# Asteroid-v4.net
KiCad netlist of a schematic drawn in EAGLE
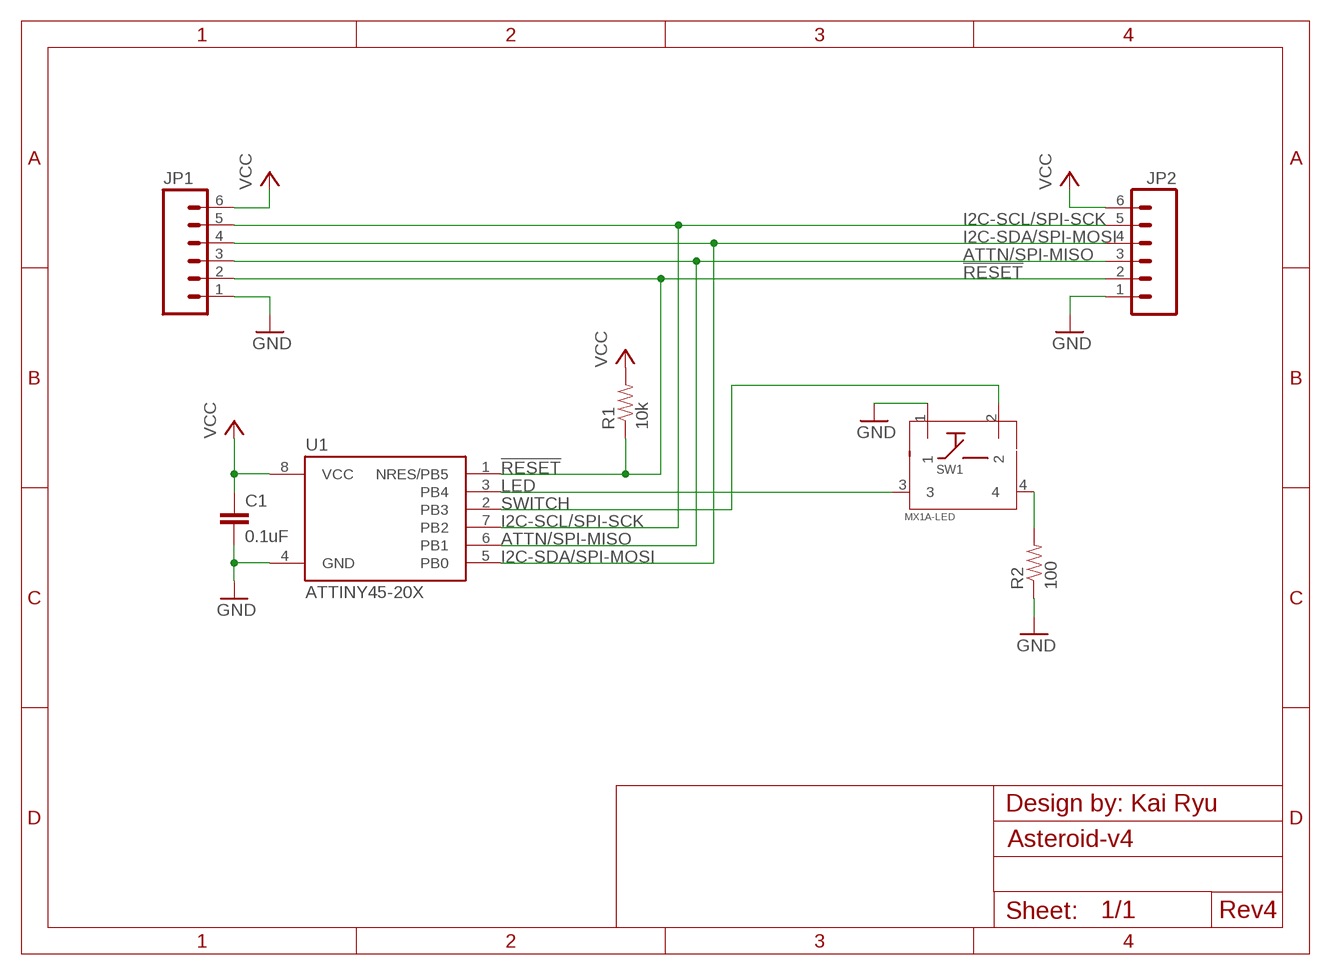
[diagram p0: schematic, sheet 1]

(export (version "E")
  (design (tool "Eeschema 10.0.6"))
  (components
    (comp (ref "C1")
      (value "0.1uF")
      (footprint "eagle-import:0603-CAP")
      (libsource (lib "eagle-import") (part "CAP0603-CAP"))
    )
    (comp (ref "JP1")
      (value "M06SIP")
      (footprint "eagle-import:1X06")
      (libsource (lib "eagle-import") (part "M06SIP"))
    )
    (comp (ref "JP2")
      (value "M06SIP")
      (footprint "eagle-import:1X06")
      (libsource (lib "eagle-import") (part "M06SIP"))
    )
    (comp (ref "R1")
      (value "10k")
      (footprint "eagle-import:0603-RES")
      (libsource (lib "eagle-import") (part "RESISTOR0603-RES"))
    )
    (comp (ref "R2")
      (value "100")
      (footprint "eagle-import:0603-RES")
      (libsource (lib "eagle-import") (part "RESISTOR0603-RES"))
    )
    (comp (ref "SW1")
      (value "MX1A-LED")
      (footprint "eagle-import:MX1A-LED")
      (libsource (lib "eagle-import") (part "MX1A-LED"))
    )
    (comp (ref "U1")
      (value "ATTINY45-20X")
      (footprint "eagle-import:TSSOP8_4MM4")
      (libsource (lib "eagle-import") (part "ATTINY45X-20"))
    )
  )
  (nets
    (net (code "1") (name "/ATTN{slash}SPI-MISO") (class "Default")
      (node (ref "JP1") (pin "3") (pinfunction "3_3") (pintype "passive"))
      (node (ref "JP2") (pin "3") (pinfunction "3_3") (pintype "passive"))
      (node (ref "U1") (pin "6") (pinfunction "PB1_6") (pintype "bidirectional"))
    )
    (net (code "2") (name "/I2C-SCL{slash}SPI-SCK") (class "Default")
      (node (ref "JP1") (pin "5") (pinfunction "5_5") (pintype "passive"))
      (node (ref "JP2") (pin "5") (pinfunction "5_5") (pintype "passive"))
      (node (ref "U1") (pin "7") (pinfunction "PB2_7") (pintype "bidirectional"))
    )
    (net (code "3") (name "/I2C-SDA{slash}SPI-MOSI") (class "Default")
      (node (ref "JP1") (pin "4") (pinfunction "4_4") (pintype "passive"))
      (node (ref "JP2") (pin "4") (pinfunction "4_4") (pintype "passive"))
      (node (ref "U1") (pin "5") (pinfunction "PB0_5") (pintype "bidirectional"))
    )
    (net (code "4") (name "/LED") (class "Default")
      (node (ref "SW1") (pin "3") (pinfunction "3_3") (pintype "passive"))
      (node (ref "U1") (pin "3") (pinfunction "PB4_3") (pintype "bidirectional"))
    )
    (net (code "5") (name "/SWITCH") (class "Default")
      (node (ref "SW1") (pin "2") (pinfunction "2_2") (pintype "passive"))
      (node (ref "U1") (pin "2") (pinfunction "PB3_2") (pintype "bidirectional"))
    )
    (net (code "6") (name "/~{RESET}") (class "Default")
      (node (ref "JP1") (pin "2") (pinfunction "2_2") (pintype "passive"))
      (node (ref "JP2") (pin "2") (pinfunction "2_2") (pintype "passive"))
      (node (ref "R1") (pin "1") (pinfunction "1_1") (pintype "passive"))
      (node (ref "U1") (pin "1") (pinfunction "NRES/PB5_1") (pintype "bidirectional"))
    )
    (net (code "7") (name "GND") (class "Default")
      (node (ref "C1") (pin "2") (pinfunction "2_2") (pintype "passive"))
      (node (ref "JP1") (pin "1") (pinfunction "1_1") (pintype "passive"))
      (node (ref "JP2") (pin "1") (pinfunction "1_1") (pintype "passive"))
      (node (ref "R2") (pin "1") (pinfunction "1_1") (pintype "passive"))
      (node (ref "SW1") (pin "1") (pinfunction "1_1") (pintype "passive"))
      (node (ref "U1") (pin "4") (pinfunction "GND_4") (pintype "power_in"))
    )
    (net (code "8") (name "Net-(R2-Pad2)") (class "Default")
      (node (ref "R2") (pin "2") (pinfunction "2_2") (pintype "passive"))
      (node (ref "SW1") (pin "4") (pinfunction "4_4") (pintype "passive"))
    )
    (net (code "9") (name "VCC") (class "Default")
      (node (ref "C1") (pin "1") (pinfunction "1_1") (pintype "passive"))
      (node (ref "JP1") (pin "6") (pinfunction "6_6") (pintype "passive"))
      (node (ref "JP2") (pin "6") (pinfunction "6_6") (pintype "passive"))
      (node (ref "R1") (pin "2") (pinfunction "2_2") (pintype "passive"))
      (node (ref "U1") (pin "8") (pinfunction "VCC_8") (pintype "power_in"))
    )
  )
)
